# Node_Schematic_EasyEDA_File.net
KiCad netlist of a schematic drawn in EasyEDA
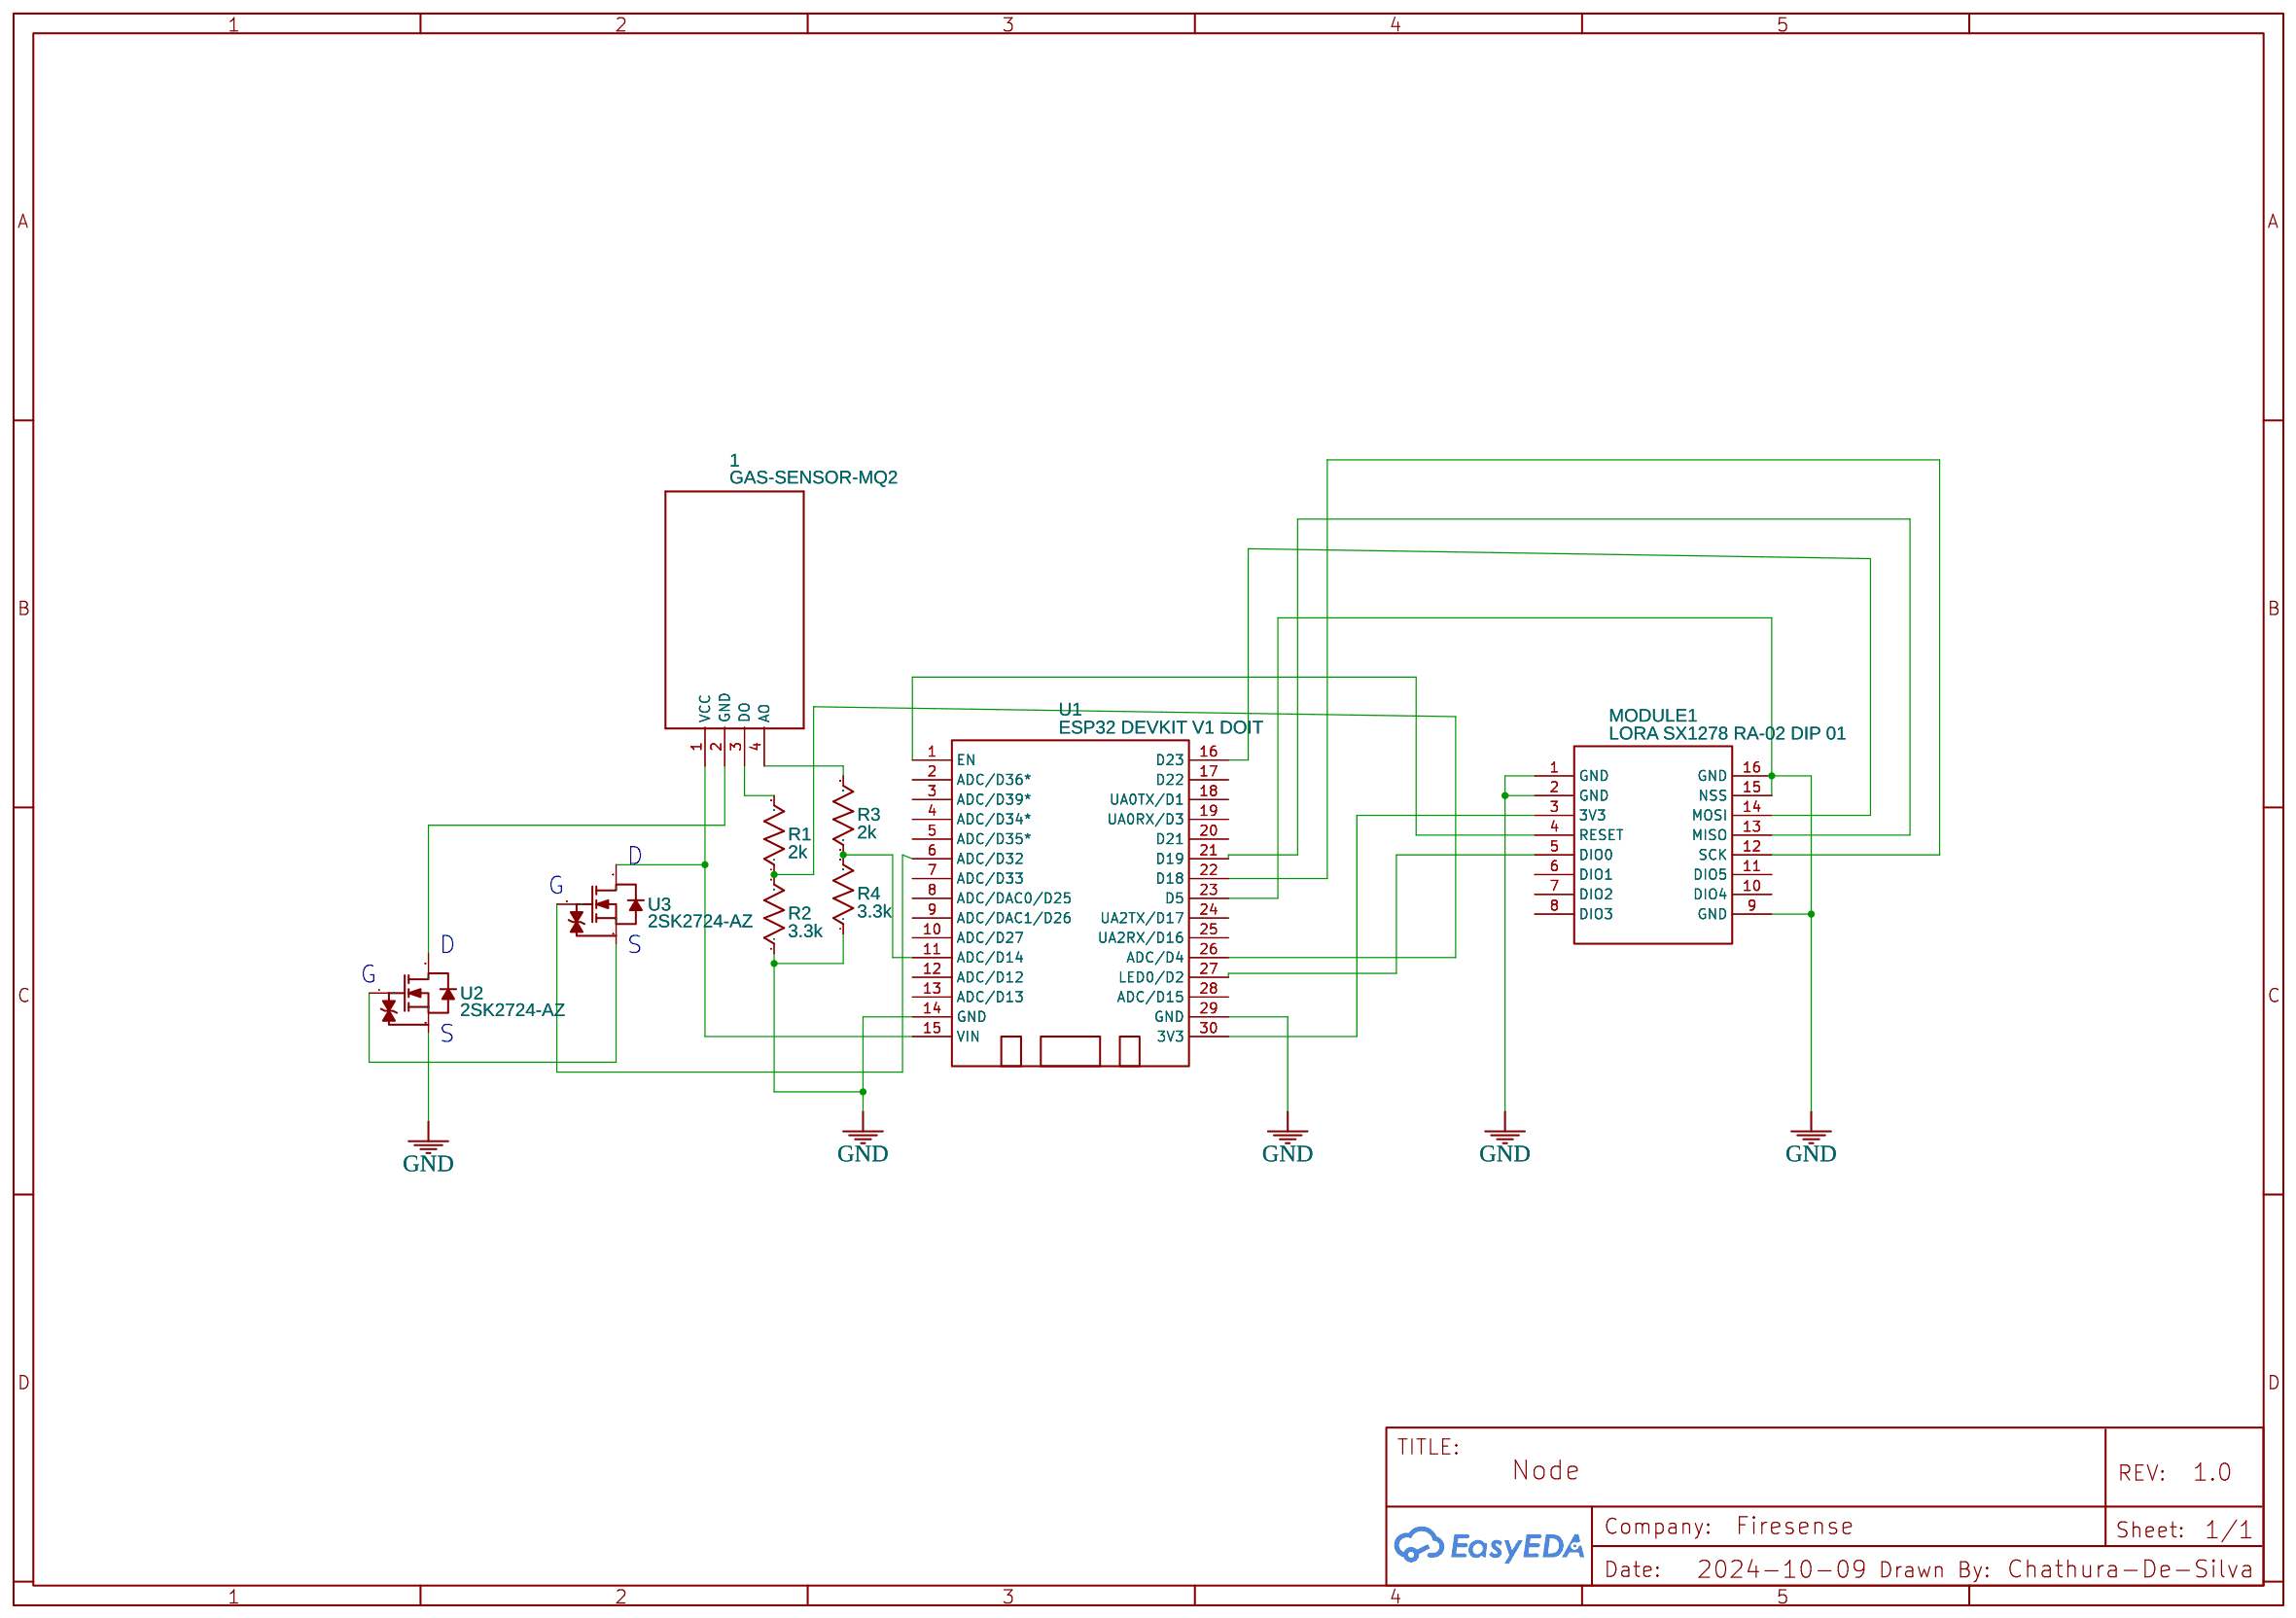
[diagram p0: schematic sheet]

(export (version "E")
  (design (tool "Eeschema 10.0.6"))
  (components
    (comp (ref "1") (value "GAS-SENSOR-MQ2") (libsource (lib "") (part "GAS-SENSOR-MQ2")))
    (comp (ref "MODULE1")
      (value "LORA SX1278 RA-02 DIP 01")
      (libsource (lib "") (part "LORA SX1278 RA-02 DIP 01"))
    )
    (comp (ref "R1") (value "2k") (libsource (lib "") (part "R_0603_US")))
    (comp (ref "R2") (value "3.3k") (libsource (lib "") (part "R_0603_US")))
    (comp (ref "R3") (value "2k") (libsource (lib "") (part "R_0603_US")))
    (comp (ref "R4") (value "3.3k") (libsource (lib "") (part "R_0603_US")))
    (comp (ref "U1") (value "ESP32 DEVKIT V1 DOIT") (libsource (lib "") (part "ESP32 DEVKIT V1 DOIT")))
    (comp (ref "U2")
      (value "2SK2724-AZ")
      (fields (field (name "Manufacturer") "RENESAS(瑞萨)/IDT"))
      (libsource (lib "") (part "2SK2724-AZ"))
    )
    (comp (ref "U3")
      (value "2SK2724-AZ")
      (fields (field (name "Manufacturer") "RENESAS(瑞萨)/IDT"))
      (libsource (lib "") (part "2SK2724-AZ"))
    )
  )
  (nets
    (net (code "1") (name "GND") (class "Default")
      (node (ref "MODULE1") (pin "1") (pinfunction "GND_1") (pintype "unspecified"))
      (node (ref "MODULE1") (pin "15") (pinfunction "NSS_15") (pintype "unspecified"))
      (node (ref "MODULE1") (pin "16") (pinfunction "GND_16") (pintype "unspecified"))
      (node (ref "MODULE1") (pin "2") (pinfunction "GND_2") (pintype "unspecified"))
      (node (ref "MODULE1") (pin "9") (pinfunction "GND_9") (pintype "unspecified"))
      (node (ref "R2") (pin "1") (pinfunction "1_1") (pintype "unspecified"))
      (node (ref "R4") (pin "1") (pinfunction "1_1") (pintype "unspecified"))
      (node (ref "U1") (pin "14") (pinfunction "GND_14") (pintype "bidirectional"))
      (node (ref "U1") (pin "23") (pinfunction "D5_23") (pintype "bidirectional"))
      (node (ref "U1") (pin "29") (pinfunction "GND_29") (pintype "bidirectional"))
      (node (ref "U2") (pin "3") (pinfunction "S_3") (pintype "unspecified"))
    )
    (net (code "2") (name "Net-(1-AO)") (class "Default")
      (node (ref "1") (pin "4") (pinfunction "AO_4") (pintype "bidirectional"))
      (node (ref "R3") (pin "2") (pinfunction "2_2") (pintype "unspecified"))
    )
    (net (code "3") (name "Net-(1-DO)") (class "Default")
      (node (ref "1") (pin "3") (pinfunction "DO_3") (pintype "bidirectional"))
      (node (ref "R1") (pin "2") (pinfunction "2_2") (pintype "unspecified"))
    )
    (net (code "4") (name "Net-(1-GND)") (class "Default")
      (node (ref "1") (pin "2") (pinfunction "GND_2") (pintype "bidirectional"))
      (node (ref "U2") (pin "2") (pinfunction "D_2") (pintype "unspecified"))
    )
    (net (code "5") (name "Net-(1-VCC)") (class "Default")
      (node (ref "1") (pin "1") (pinfunction "VCC_1") (pintype "bidirectional"))
      (node (ref "U1") (pin "15") (pinfunction "VIN_15") (pintype "input"))
      (node (ref "U3") (pin "2") (pinfunction "D_2") (pintype "unspecified"))
    )
    (net (code "6") (name "Net-(MODULE1-3V3)") (class "Default")
      (node (ref "MODULE1") (pin "3") (pinfunction "3V3_3") (pintype "unspecified"))
      (node (ref "U1") (pin "30") (pinfunction "3V3_30") (pintype "bidirectional"))
    )
    (net (code "7") (name "Net-(MODULE1-DIO0)") (class "Default")
      (node (ref "MODULE1") (pin "5") (pinfunction "DIO0_5") (pintype "unspecified"))
      (node (ref "U1") (pin "27") (pinfunction "LED0/D2_27") (pintype "bidirectional"))
    )
    (net (code "8") (name "Net-(MODULE1-MISO)") (class "Default")
      (node (ref "MODULE1") (pin "13") (pinfunction "MISO_13") (pintype "unspecified"))
      (node (ref "U1") (pin "21") (pinfunction "D19_21") (pintype "bidirectional"))
    )
    (net (code "9") (name "Net-(MODULE1-MOSI)") (class "Default")
      (node (ref "MODULE1") (pin "14") (pinfunction "MOSI_14") (pintype "unspecified"))
      (node (ref "U1") (pin "16") (pinfunction "D23_16") (pintype "bidirectional"))
    )
    (net (code "10") (name "Net-(MODULE1-RESET)") (class "Default")
      (node (ref "MODULE1") (pin "4") (pinfunction "RESET_4") (pintype "unspecified"))
      (node (ref "U1") (pin "1") (pinfunction "EN_1") (pintype "bidirectional"))
    )
    (net (code "11") (name "Net-(MODULE1-SCK)") (class "Default")
      (node (ref "MODULE1") (pin "12") (pinfunction "SCK_12") (pintype "unspecified"))
      (node (ref "U1") (pin "22") (pinfunction "D18_22") (pintype "bidirectional"))
    )
    (net (code "12") (name "Net-(U1-ADC{slash}D4)") (class "Default")
      (node (ref "R1") (pin "1") (pinfunction "1_1") (pintype "unspecified"))
      (node (ref "R2") (pin "2") (pinfunction "2_2") (pintype "unspecified"))
      (node (ref "U1") (pin "26") (pinfunction "ADC/D4_26") (pintype "bidirectional"))
    )
    (net (code "13") (name "Net-(U1-ADC{slash}D14)") (class "Default")
      (node (ref "R3") (pin "1") (pinfunction "1_1") (pintype "unspecified"))
      (node (ref "R4") (pin "2") (pinfunction "2_2") (pintype "unspecified"))
      (node (ref "U1") (pin "11") (pinfunction "ADC/D14_11") (pintype "bidirectional"))
    )
    (net (code "14") (name "Net-(U1-ADC{slash}D32)") (class "Default")
      (node (ref "U1") (pin "6") (pinfunction "ADC/D32_6") (pintype "bidirectional"))
      (node (ref "U3") (pin "1") (pinfunction "G_1") (pintype "unspecified"))
    )
    (net (code "15") (name "Net-(U2-G)") (class "Default")
      (node (ref "U2") (pin "1") (pinfunction "G_1") (pintype "unspecified"))
      (node (ref "U3") (pin "3") (pinfunction "S_3") (pintype "unspecified"))
    )
    (net (code "16") (name "unconnected-(MODULE1-DIO1-Pad6)") (class "Default")
      (node (ref "MODULE1") (pin "6") (pinfunction "DIO1_6") (pintype "unspecified"))
    )
    (net (code "17") (name "unconnected-(MODULE1-DIO2-Pad7)") (class "Default")
      (node (ref "MODULE1") (pin "7") (pinfunction "DIO2_7") (pintype "unspecified"))
    )
    (net (code "18") (name "unconnected-(MODULE1-DIO3-Pad8)") (class "Default")
      (node (ref "MODULE1") (pin "8") (pinfunction "DIO3_8") (pintype "unspecified"))
    )
    (net (code "19") (name "unconnected-(MODULE1-DIO4-Pad10)") (class "Default")
      (node (ref "MODULE1") (pin "10") (pinfunction "DIO4_10") (pintype "unspecified"))
    )
    (net (code "20") (name "unconnected-(MODULE1-DIO5-Pad11)") (class "Default")
      (node (ref "MODULE1") (pin "11") (pinfunction "DIO5_11") (pintype "unspecified"))
    )
    (net (code "21") (name "unconnected-(U1-ADC{slash}D12-Pad12)") (class "Default")
      (node (ref "U1") (pin "12") (pinfunction "ADC/D12_12") (pintype "bidirectional"))
    )
    (net (code "22") (name "unconnected-(U1-ADC{slash}D13-Pad13)") (class "Default")
      (node (ref "U1") (pin "13") (pinfunction "ADC/D13_13") (pintype "bidirectional"))
    )
    (net (code "23") (name "unconnected-(U1-ADC{slash}D15-Pad28)") (class "Default")
      (node (ref "U1") (pin "28") (pinfunction "ADC/D15_28") (pintype "bidirectional"))
    )
    (net (code "24") (name "unconnected-(U1-ADC{slash}D27-Pad10)") (class "Default")
      (node (ref "U1") (pin "10") (pinfunction "ADC/D27_10") (pintype "bidirectional"))
    )
    (net (code "25") (name "unconnected-(U1-ADC{slash}D33-Pad7)") (class "Default")
      (node (ref "U1") (pin "7") (pinfunction "ADC/D33_7") (pintype "bidirectional"))
    )
    (net (code "26") (name "unconnected-(U1-ADC{slash}D34*-Pad4)") (class "Default")
      (node (ref "U1") (pin "4") (pinfunction "ADC/D34*_4") (pintype "input"))
    )
    (net (code "27") (name "unconnected-(U1-ADC{slash}D35*-Pad5)") (class "Default")
      (node (ref "U1") (pin "5") (pinfunction "ADC/D35*_5") (pintype "input"))
    )
    (net (code "28") (name "unconnected-(U1-ADC{slash}D36*-Pad2)") (class "Default")
      (node (ref "U1") (pin "2") (pinfunction "ADC/D36*_2") (pintype "input"))
    )
    (net (code "29") (name "unconnected-(U1-ADC{slash}D39*-Pad3)") (class "Default")
      (node (ref "U1") (pin "3") (pinfunction "ADC/D39*_3") (pintype "input"))
    )
    (net (code "30") (name "unconnected-(U1-ADC{slash}DAC0{slash}D25-Pad8)") (class "Default")
      (node (ref "U1") (pin "8") (pinfunction "ADC/DAC0/D25_8") (pintype "bidirectional"))
    )
    (net (code "31") (name "unconnected-(U1-ADC{slash}DAC1{slash}D26-Pad9)") (class "Default")
      (node (ref "U1") (pin "9") (pinfunction "ADC/DAC1/D26_9") (pintype "bidirectional"))
    )
    (net (code "32") (name "unconnected-(U1-D21-Pad20)") (class "Default")
      (node (ref "U1") (pin "20") (pinfunction "D21_20") (pintype "bidirectional"))
    )
    (net (code "33") (name "unconnected-(U1-D22-Pad17)") (class "Default")
      (node (ref "U1") (pin "17") (pinfunction "D22_17") (pintype "bidirectional"))
    )
    (net (code "34") (name "unconnected-(U1-UA0RX{slash}D3-Pad19)") (class "Default")
      (node (ref "U1") (pin "19") (pinfunction "UA0RX/D3_19") (pintype "bidirectional"))
    )
    (net (code "35") (name "unconnected-(U1-UA0TX{slash}D1-Pad18)") (class "Default")
      (node (ref "U1") (pin "18") (pinfunction "UA0TX/D1_18") (pintype "bidirectional"))
    )
    (net (code "36") (name "unconnected-(U1-UA2RX{slash}D16-Pad25)") (class "Default")
      (node (ref "U1") (pin "25") (pinfunction "UA2RX/D16_25") (pintype "bidirectional"))
    )
    (net (code "37") (name "unconnected-(U1-UA2TX{slash}D17-Pad24)") (class "Default")
      (node (ref "U1") (pin "24") (pinfunction "UA2TX/D17_24") (pintype "bidirectional"))
    )
  )
)
